# LaunchController1.net
KiCad netlist of a schematic drawn in EAGLE
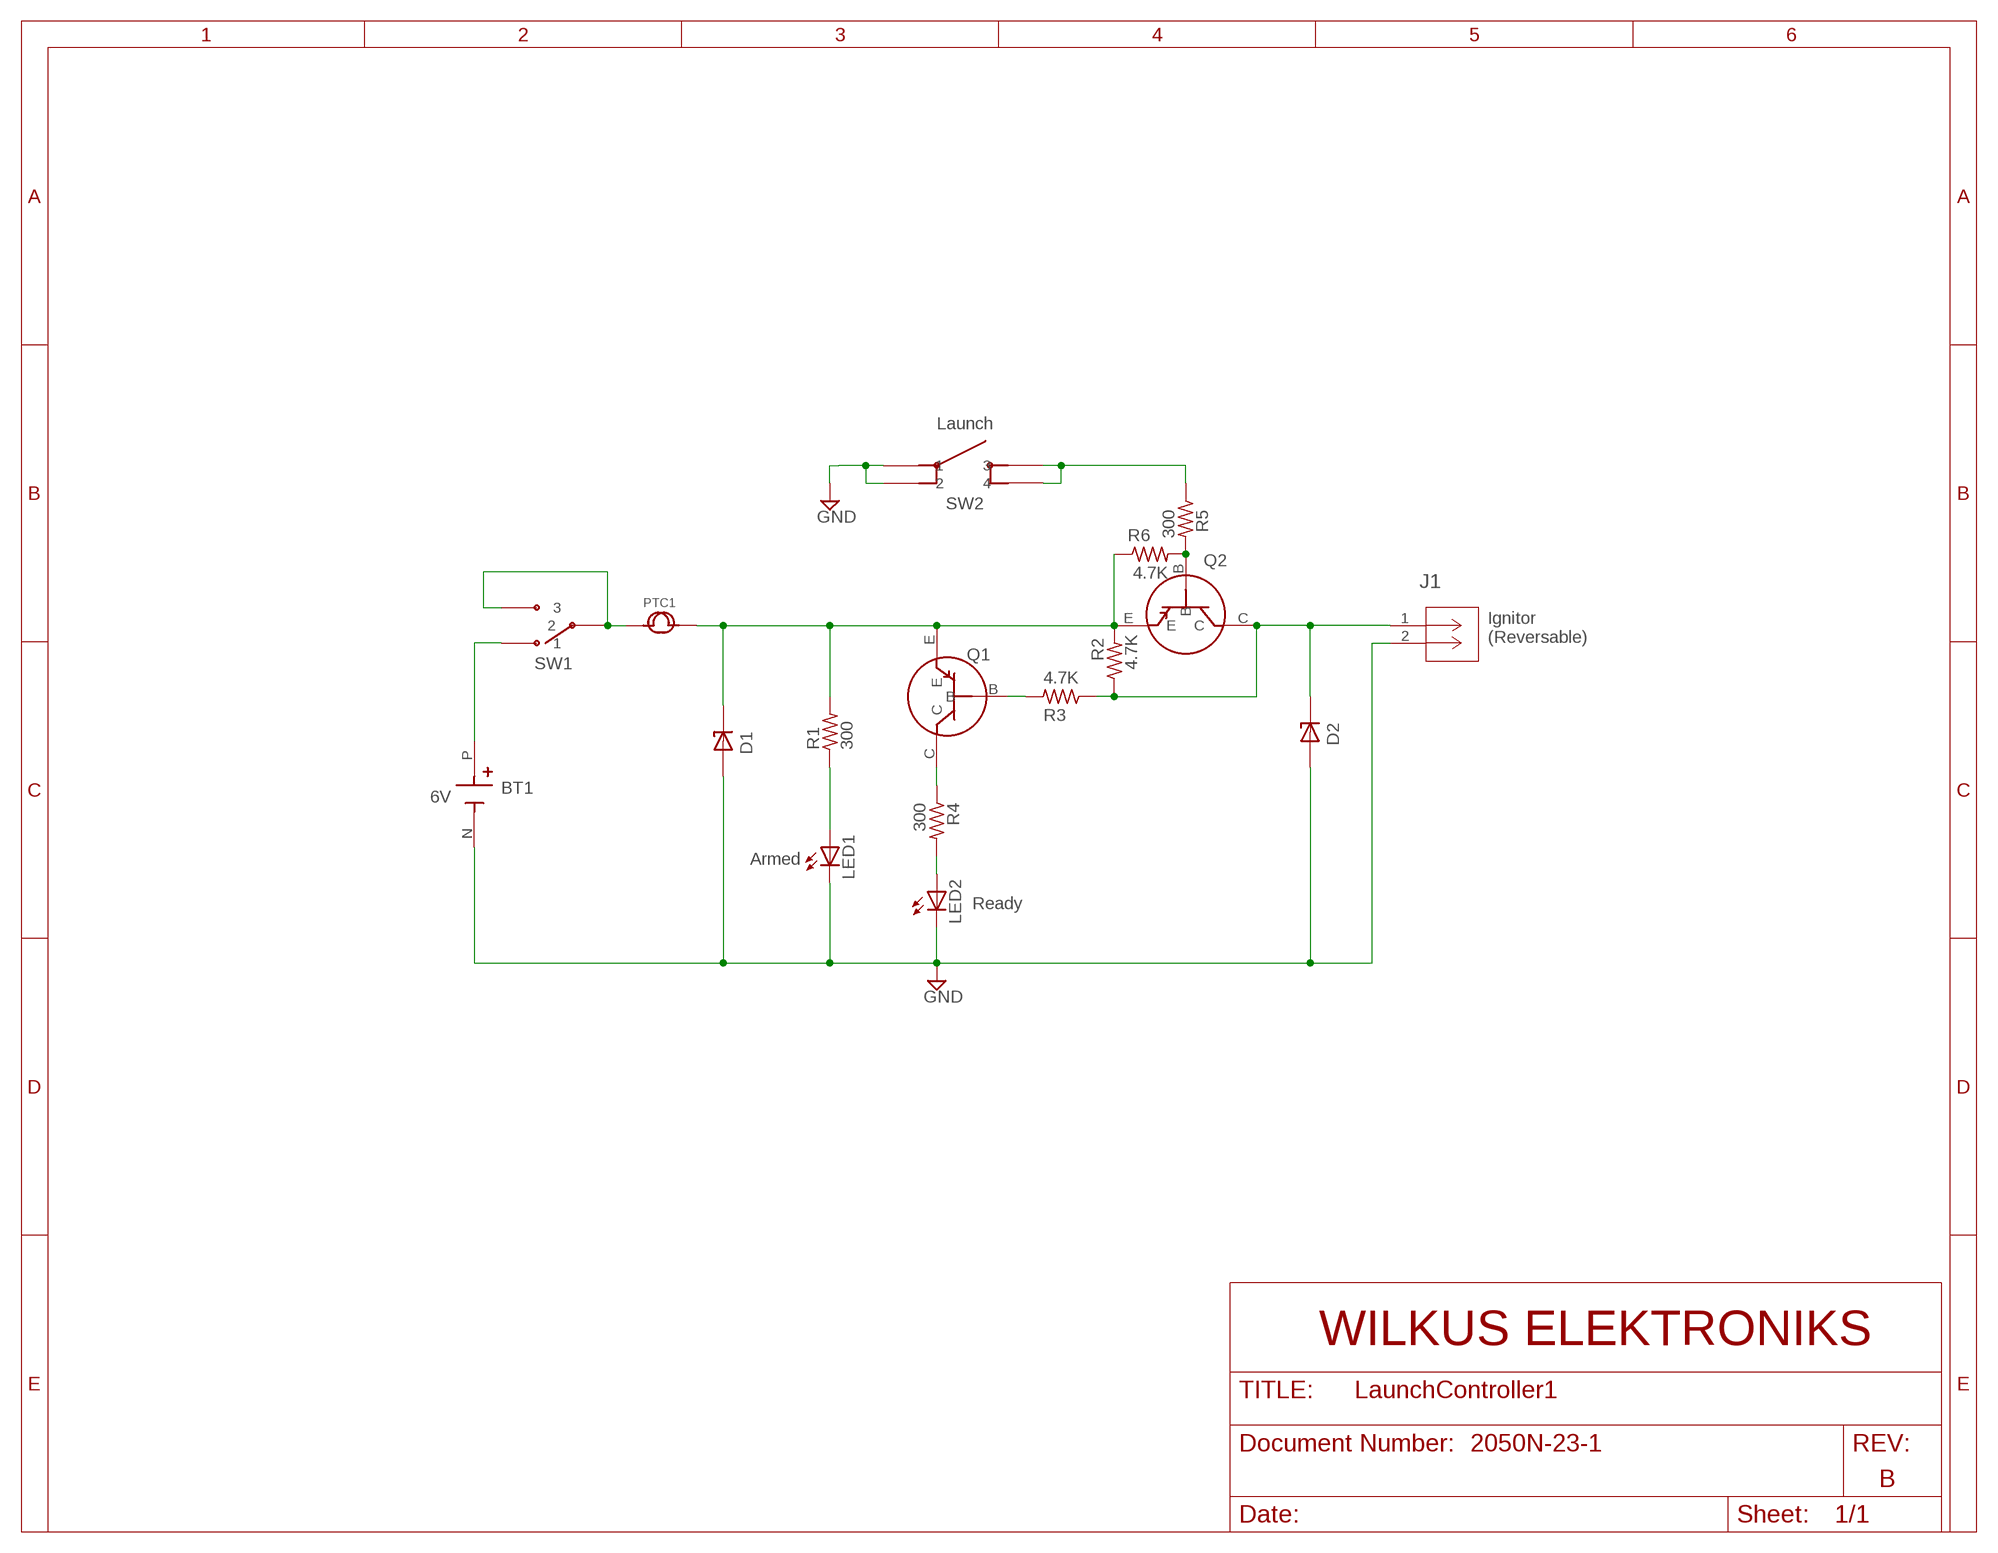
[diagram p0: schematic, sheet 1]

(export (version "E")
  (design (tool "Eeschema 10.0.6"))
  (components
    (comp (ref "BT1")
      (value "6V")
      (footprint "eagle-import:BAT_2477")
      (fields (field (name "MF") "Keystone Electronics") (field (name "MP") "2477"))
      (libsource (lib "eagle-import") (part "2477"))
    )
    (comp (ref "D1")
      (value "P6KE75CA")
      (footprint "eagle-import:DIOAD1300W80L670D310")
      (fields (field (name "MF") "Littelfuse Inc."))
      (libsource (lib "eagle-import") (part "P6KE75CA"))
    )
    (comp (ref "D2")
      (value "P6KE75CA")
      (footprint "eagle-import:DIOAD1300W80L670D310")
      (fields (field (name "MF") "Littelfuse Inc."))
      (libsource (lib "eagle-import") (part "P6KE75CA"))
    )
    (comp (ref "J1")
      (value "691137710002")
      (footprint "eagle-import:CONN2_710002_WRE")
      (fields (field (name "COPYRIGHT") "Copyright (C) 2023 Ultra Librarian. All rights reserved."))
      (libsource (lib "eagle-import") (part "691137710002"))
    )
    (comp (ref "LED1")
      (value "LED5MM")
      (footprint "eagle-import:LED5MM")
      (libsource (lib "eagle-import") (part "LED5MM"))
    )
    (comp (ref "LED2")
      (value "LED5MM")
      (footprint "eagle-import:LED5MM")
      (libsource (lib "eagle-import") (part "LED5MM"))
    )
    (comp (ref "PTC1")
      (value "0ZRG0120FF2E")
      (footprint "eagle-import:0ZRG")
      (libsource (lib "eagle-import") (part "0ZRG0120FF2E"))
    )
    (comp (ref "Q1")
      (value "BJT_PNP")
      (footprint "eagle-import:TO92-")
      (libsource (lib "eagle-import") (part "BJT_PNP"))
    )
    (comp (ref "Q2")
      (value "BJT_PNP")
      (footprint "eagle-import:TO92-")
      (libsource (lib "eagle-import") (part "BJT_PNP"))
    )
    (comp (ref "R1")
      (value "300")
      (footprint "eagle-import:0309_12")
      (libsource (lib "eagle-import") (part "RES_0.5W_TH"))
    )
    (comp (ref "R2")
      (value "4.7K")
      (footprint "eagle-import:0309_12")
      (libsource (lib "eagle-import") (part "RES_0.5W_TH"))
    )
    (comp (ref "R3")
      (value "4.7K")
      (footprint "eagle-import:0309_12")
      (libsource (lib "eagle-import") (part "RES_0.5W_TH"))
    )
    (comp (ref "R4")
      (value "300")
      (footprint "eagle-import:0309_12")
      (libsource (lib "eagle-import") (part "RES_0.5W_TH"))
    )
    (comp (ref "R5")
      (value "300")
      (footprint "eagle-import:0309_12")
      (libsource (lib "eagle-import") (part "RES_0.5W_TH"))
    )
    (comp (ref "R6")
      (value "4.7K")
      (footprint "eagle-import:0309_12")
      (libsource (lib "eagle-import") (part "RES_0.5W_TH"))
    )
    (comp (ref "SW1")
      (value "ANT11SF1CQE")
      (footprint "eagle-import:ANT11SF1CQE")
      (libsource (lib "eagle-import") (part "ANT11SF1CQE"))
    )
    (comp (ref "SW2")
      (value "D6R40F2LFS")
      (footprint "eagle-import:D6R40F2LFS")
      (libsource (lib "eagle-import") (part "D6R40F2LFS"))
    )
  )
  (nets
    (net (code "1") (name "GND") (class "Default")
      (node (ref "BT1") (pin "N") (pinfunction "NEG_N") (pintype "passive"))
      (node (ref "D1") (pin "A") (pinfunction "A_A") (pintype "passive"))
      (node (ref "D2") (pin "A") (pinfunction "A_A") (pintype "passive"))
      (node (ref "J1") (pin "2") (pinfunction "2_2") (pintype "passive"))
      (node (ref "LED1") (pin "K") (pinfunction "C_K") (pintype "passive"))
      (node (ref "LED2") (pin "K") (pinfunction "C_K") (pintype "passive"))
      (node (ref "SW2") (pin "P$1") (pinfunction "1_P$1") (pintype "bidirectional"))
      (node (ref "SW2") (pin "P$2") (pinfunction "2_P$2") (pintype "bidirectional"))
    )
    (net (code "2") (name "Net-(BT1-POS)") (class "Default")
      (node (ref "BT1") (pin "P") (pinfunction "POS_P") (pintype "passive"))
      (node (ref "SW1") (pin "P$1") (pinfunction "1_P$1") (pintype "bidirectional"))
    )
    (net (code "3") (name "Net-(D1-PadC)") (class "Default")
      (node (ref "D1") (pin "C") (pinfunction "C_C") (pintype "passive"))
      (node (ref "PTC1") (pin "2") (pinfunction "2_2") (pintype "bidirectional"))
      (node (ref "Q1") (pin "E") (pinfunction "E_E") (pintype "bidirectional"))
      (node (ref "Q2") (pin "E") (pinfunction "E_E") (pintype "bidirectional"))
      (node (ref "R1") (pin "2") (pinfunction "2_2") (pintype "passive"))
      (node (ref "R2") (pin "2") (pinfunction "2_2") (pintype "passive"))
      (node (ref "R6") (pin "1") (pinfunction "1_1") (pintype "passive"))
    )
    (net (code "4") (name "Net-(D2-PadC)") (class "Default")
      (node (ref "D2") (pin "C") (pinfunction "C_C") (pintype "passive"))
      (node (ref "J1") (pin "1") (pinfunction "1_1") (pintype "passive"))
      (node (ref "Q2") (pin "C") (pinfunction "C_C") (pintype "bidirectional"))
      (node (ref "R2") (pin "1") (pinfunction "1_1") (pintype "passive"))
      (node (ref "R3") (pin "1") (pinfunction "1_1") (pintype "passive"))
    )
    (net (code "5") (name "Net-(LED1-PadA)") (class "Default")
      (node (ref "LED1") (pin "A") (pinfunction "A_A") (pintype "passive"))
      (node (ref "R1") (pin "1") (pinfunction "1_1") (pintype "passive"))
    )
    (net (code "6") (name "Net-(LED2-PadA)") (class "Default")
      (node (ref "LED2") (pin "A") (pinfunction "A_A") (pintype "passive"))
      (node (ref "R4") (pin "2") (pinfunction "2_2") (pintype "passive"))
    )
    (net (code "7") (name "Net-(Q1-PadB)") (class "Default")
      (node (ref "Q1") (pin "B") (pinfunction "B_B") (pintype "bidirectional"))
      (node (ref "R3") (pin "2") (pinfunction "2_2") (pintype "passive"))
    )
    (net (code "8") (name "Net-(Q1-PadC)") (class "Default")
      (node (ref "Q1") (pin "C") (pinfunction "C_C") (pintype "bidirectional"))
      (node (ref "R4") (pin "1") (pinfunction "1_1") (pintype "passive"))
    )
    (net (code "9") (name "Net-(Q2-PadB)") (class "Default")
      (node (ref "Q2") (pin "B") (pinfunction "B_B") (pintype "bidirectional"))
      (node (ref "R5") (pin "2") (pinfunction "2_2") (pintype "passive"))
      (node (ref "R6") (pin "2") (pinfunction "2_2") (pintype "passive"))
    )
    (net (code "10") (name "Net-(SW1-2)") (class "Default")
      (node (ref "PTC1") (pin "1") (pinfunction "1_1") (pintype "bidirectional"))
      (node (ref "SW1") (pin "P$2") (pinfunction "2_P$2") (pintype "bidirectional"))
      (node (ref "SW1") (pin "P$3") (pinfunction "3_P$3") (pintype "bidirectional"))
    )
    (net (code "11") (name "Net-(SW2-3)") (class "Default")
      (node (ref "R5") (pin "1") (pinfunction "1_1") (pintype "passive"))
      (node (ref "SW2") (pin "P$3") (pinfunction "3_P$3") (pintype "bidirectional"))
      (node (ref "SW2") (pin "P$4") (pinfunction "4_P$4") (pintype "bidirectional"))
    )
  )
)
